# Schematic_DeLonghi_CP_original.net
KiCad netlist of a schematic drawn in EasyEDA
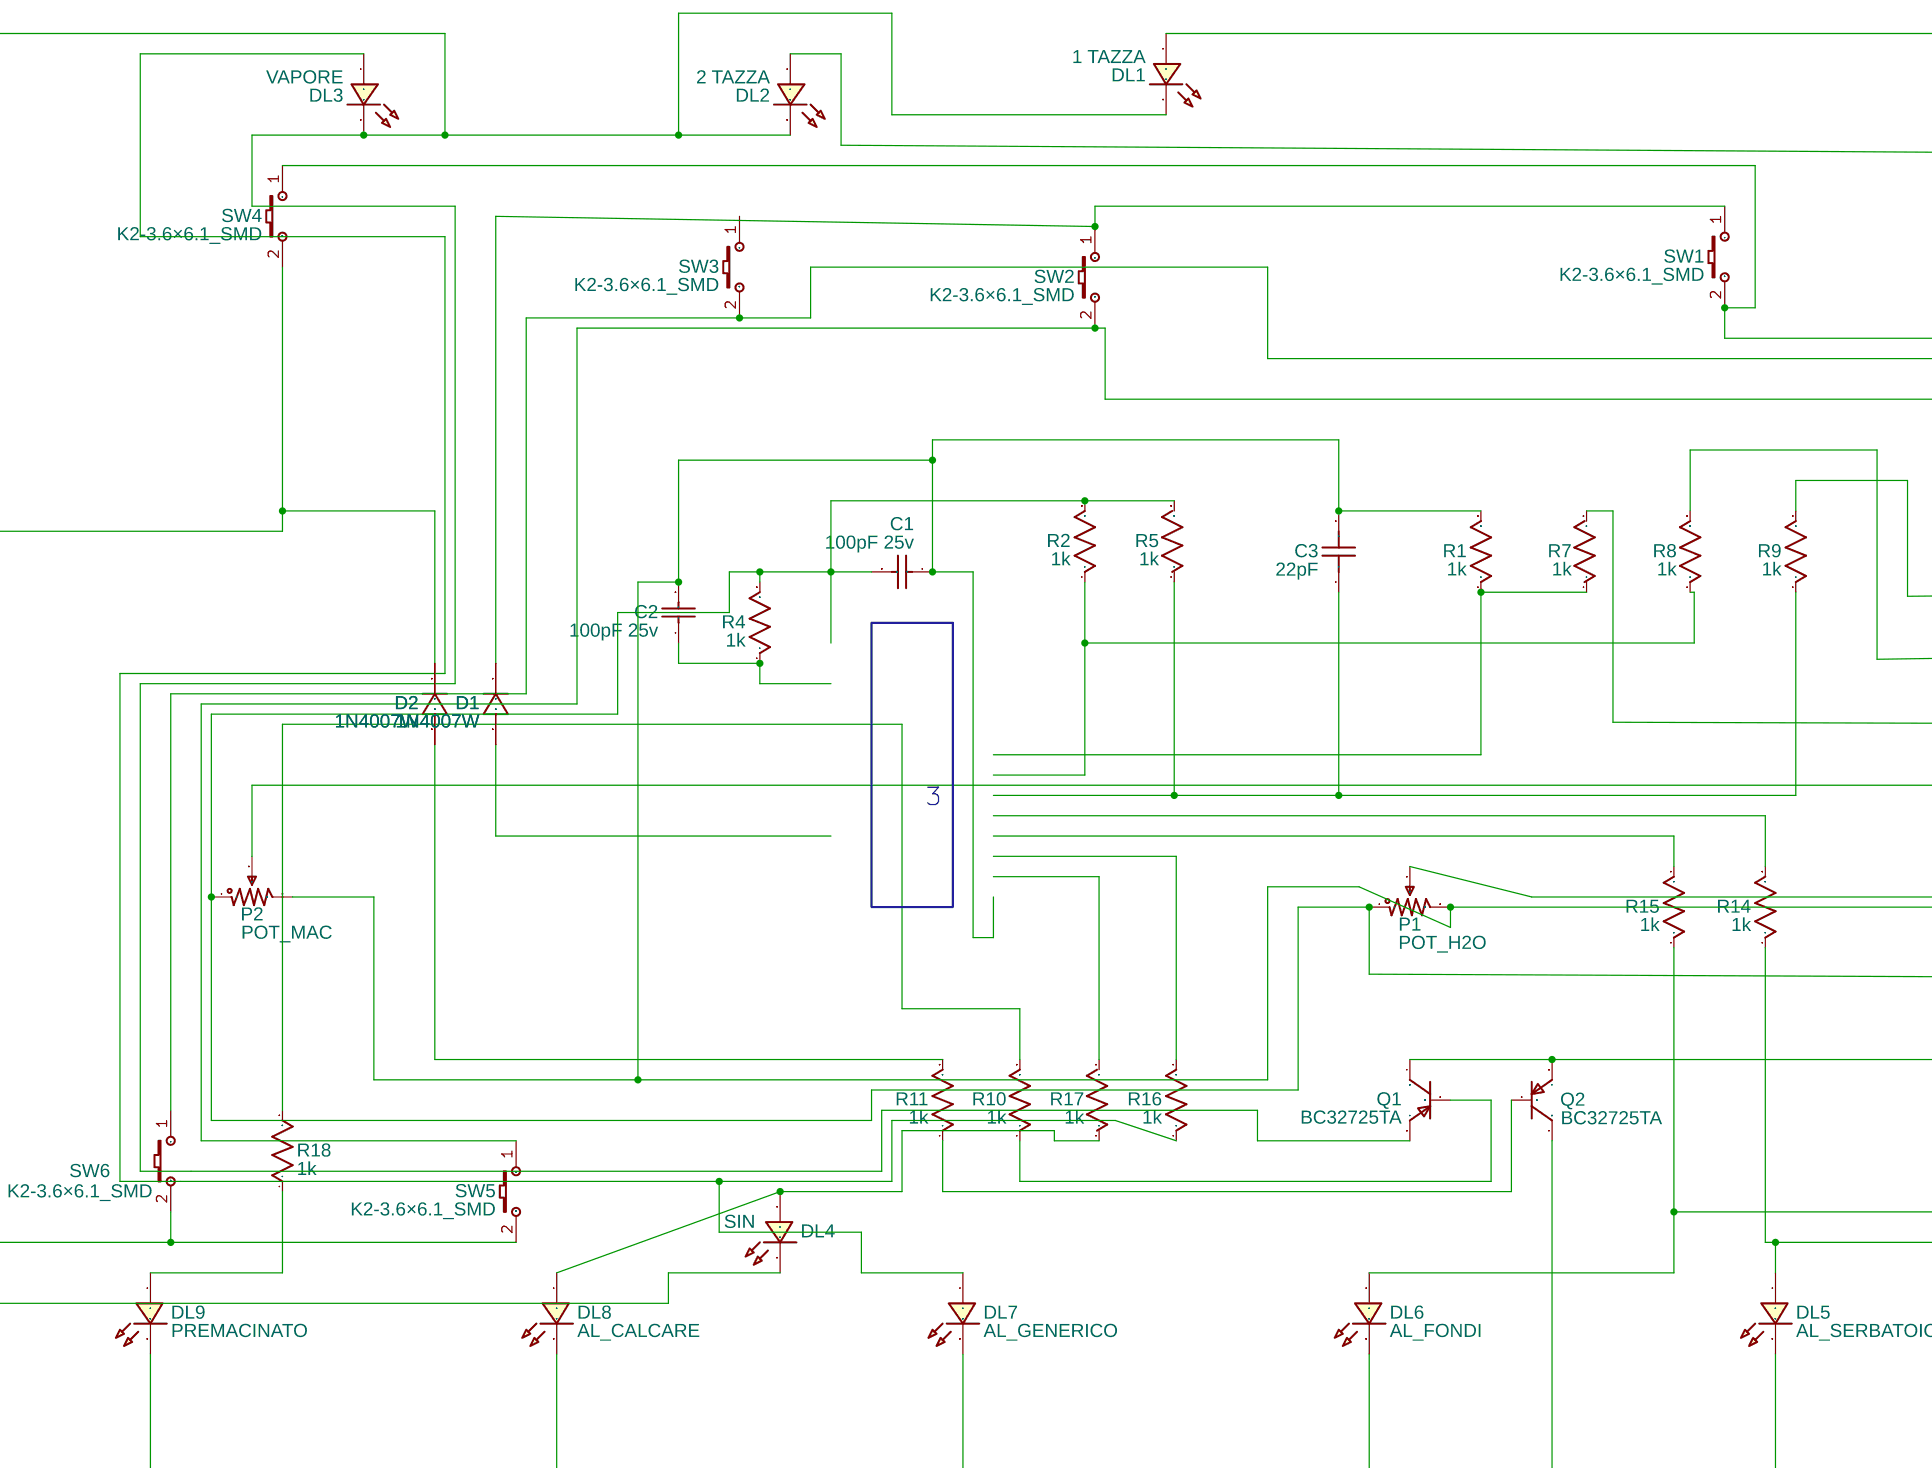
[diagram p0: schematic sheet]

(export (version "E")
  (design (tool "Eeschema 10.0.6"))
  (components
    (comp (ref "C1") (value "100pF 25v") (libsource (lib "") (part "100pF (101) 25V")))
    (comp (ref "C2") (value "100pF 25v") (libsource (lib "") (part "100pF (101) 25V_1")))
    (comp (ref "C3")
      (value "22pF")
      (fields
        (field (name "BOM_Manufacturer Part") "08051A220JAT2A")
        (field (name "BOM_Supplier Part") "C382073")
      )
      (libsource (lib "") (part "08051A220JAT2A"))
    )
    (comp (ref "D1")
      (value "1N4007W")
      (fields (field (name "BOM_Supplier Part") "C328592"))
      (libsource (lib "") (part "1N4007W"))
    )
    (comp (ref "D2")
      (value "1N4007W")
      (fields (field (name "BOM_Supplier Part") "C328592"))
      (libsource (lib "") (part "1N4007W"))
    )
    (comp (ref "DL1")
      (value "1 TAZZA")
      (fields
        (field (name "BOM_Manufacturer Part") "19-217/R6C-AL1M2VY/3T")
        (field (name "BOM_Supplier Part") "C72044")
      )
      (libsource (lib "") (part "LED-0603_R_1"))
    )
    (comp (ref "DL2")
      (value "2 TAZZA")
      (fields
        (field (name "BOM_Manufacturer Part") "19-217/R6C-AL1M2VY/3T")
        (field (name "BOM_Supplier Part") "C72044")
      )
      (libsource (lib "") (part "LED-0603_R_1"))
    )
    (comp (ref "DL3")
      (value "VAPORE")
      (fields
        (field (name "BOM_Manufacturer Part") "19-217/R6C-AL1M2VY/3T")
        (field (name "BOM_Supplier Part") "C72044")
      )
      (libsource (lib "") (part "LED-0603_R_1"))
    )
    (comp (ref "DL4")
      (value "SIN")
      (fields
        (field (name "BOM_Manufacturer Part") "19-217/R6C-AL1M2VY/3T")
        (field (name "BOM_Supplier Part") "C72044")
      )
      (libsource (lib "") (part "LED-0603_R"))
    )
    (comp (ref "DL5")
      (value "AL_SERBATOIO")
      (fields
        (field (name "BOM_Manufacturer Part") "19-217/R6C-AL1M2VY/3T")
        (field (name "BOM_Supplier Part") "C72044")
      )
      (libsource (lib "") (part "LED-0603_R"))
    )
    (comp (ref "DL6")
      (value "AL_FONDI")
      (fields
        (field (name "BOM_Manufacturer Part") "19-217/R6C-AL1M2VY/3T")
        (field (name "BOM_Supplier Part") "C72044")
      )
      (libsource (lib "") (part "LED-0603_R"))
    )
    (comp (ref "DL7")
      (value "AL_GENERICO")
      (fields
        (field (name "BOM_Manufacturer Part") "19-217/R6C-AL1M2VY/3T")
        (field (name "BOM_Supplier Part") "C72044")
      )
      (libsource (lib "") (part "LED-0603_R"))
    )
    (comp (ref "DL8")
      (value "AL_CALCARE")
      (fields
        (field (name "BOM_Manufacturer Part") "19-217/R6C-AL1M2VY/3T")
        (field (name "BOM_Supplier Part") "C72044")
      )
      (libsource (lib "") (part "LED-0603_R"))
    )
    (comp (ref "DL9")
      (value "PREMACINATO")
      (fields
        (field (name "BOM_Manufacturer Part") "19-217/R6C-AL1M2VY/3T")
        (field (name "BOM_Supplier Part") "C72044")
      )
      (libsource (lib "") (part "LED-0603_R"))
    )
    (comp (ref "P1") (value "POT_H2O") (libsource (lib "") (part "R_3386P_US")))
    (comp (ref "P2") (value "POT_MAC") (libsource (lib "") (part "R_3386P_US")))
    (comp (ref "Q1")
      (value "BC32725TA")
      (fields (field (name "BOM_Supplier Part") "C236948"))
      (libsource (lib "") (part "BC32725TA_1"))
    )
    (comp (ref "Q2")
      (value "BC32725TA")
      (fields (field (name "BOM_Supplier Part") "C236948"))
      (libsource (lib "") (part "BC32725TA"))
    )
    (comp (ref "R1") (value "1k") (libsource (lib "") (part "R_0201_US")))
    (comp (ref "R2") (value "1k") (libsource (lib "") (part "R_0201_US")))
    (comp (ref "R4") (value "1k") (libsource (lib "") (part "R_0201_US")))
    (comp (ref "R5") (value "1k") (libsource (lib "") (part "R_0201_US_2")))
    (comp (ref "R7") (value "1k") (libsource (lib "") (part "R_0201_US_2")))
    (comp (ref "R8") (value "1k") (libsource (lib "") (part "R_0201_US")))
    (comp (ref "R9") (value "1k") (libsource (lib "") (part "R_0201_US")))
    (comp (ref "R10") (value "1k") (libsource (lib "") (part "R_0201_US")))
    (comp (ref "R11") (value "1k") (libsource (lib "") (part "R_0201_US")))
    (comp (ref "R14") (value "1k") (libsource (lib "") (part "R_0201_US")))
    (comp (ref "R15") (value "1k") (libsource (lib "") (part "R_0201_US")))
    (comp (ref "R16") (value "1k") (libsource (lib "") (part "R_0201_US")))
    (comp (ref "R17") (value "1k") (libsource (lib "") (part "R_0201_US_2")))
    (comp (ref "R18") (value "1k") (libsource (lib "") (part "R_0201_US_1")))
    (comp (ref "SW1")
      (value "K2-3.6×6.1_SMD")
      (fields
        (field (name "BOM_Manufacturer Part") "K2-1107ST-A4SW-06")
        (field (name "BOM_Supplier Part") "C118141")
      )
      (libsource (lib "") (part "K2-3.6×6.1_SMD"))
    )
    (comp (ref "SW2")
      (value "K2-3.6×6.1_SMD")
      (fields
        (field (name "BOM_Manufacturer Part") "K2-1107ST-A4SW-06")
        (field (name "BOM_Supplier Part") "C118141")
      )
      (libsource (lib "") (part "K2-3.6×6.1_SMD"))
    )
    (comp (ref "SW3")
      (value "K2-3.6×6.1_SMD")
      (fields
        (field (name "BOM_Manufacturer Part") "K2-1107ST-A4SW-06")
        (field (name "BOM_Supplier Part") "C118141")
      )
      (libsource (lib "") (part "K2-3.6×6.1_SMD"))
    )
    (comp (ref "SW4")
      (value "K2-3.6×6.1_SMD")
      (fields
        (field (name "BOM_Manufacturer Part") "K2-1107ST-A4SW-06")
        (field (name "BOM_Supplier Part") "C118141")
      )
      (libsource (lib "") (part "K2-3.6×6.1_SMD"))
    )
    (comp (ref "SW5")
      (value "K2-3.6×6.1_SMD")
      (fields
        (field (name "BOM_Manufacturer Part") "K2-1107ST-A4SW-06")
        (field (name "BOM_Supplier Part") "C118141")
      )
      (libsource (lib "") (part "K2-3.6×6.1_SMD"))
    )
    (comp (ref "SW6")
      (value "K2-3.6×6.1_SMD")
      (fields
        (field (name "BOM_Manufacturer Part") "K2-1107ST-A4SW-06")
        (field (name "BOM_Supplier Part") "C118141")
      )
      (libsource (lib "") (part "K2-3.6×6.1_SMD"))
    )
  )
  (nets
    (net (code "1") (name "Net-(C1-Pad1)") (class "Default")
      (node (ref "C1") (pin "1") (pinfunction "1_1") (pintype "input"))
      (node (ref "C2") (pin "2") (pinfunction "2_2") (pintype "input"))
      (node (ref "C3") (pin "2") (pinfunction "2_2") (pintype "unspecified"))
      (node (ref "P1") (pin "3") (pinfunction "3_3") (pintype "unspecified"))
      (node (ref "P2") (pin "3") (pinfunction "3_3") (pintype "unspecified"))
      (node (ref "R1") (pin "2") (pinfunction "2_2") (pintype "unspecified"))
    )
    (net (code "2") (name "Net-(C1-Pad2)") (class "Default")
      (node (ref "C1") (pin "2") (pinfunction "2_2") (pintype "input"))
      (node (ref "P1") (pin "1") (pinfunction "1_1") (pintype "unspecified"))
      (node (ref "P2") (pin "1") (pinfunction "1_1") (pintype "unspecified"))
      (node (ref "R2") (pin "2") (pinfunction "2_2") (pintype "unspecified"))
      (node (ref "R4") (pin "2") (pinfunction "2_2") (pintype "unspecified"))
      (node (ref "R5") (pin "2") (pinfunction "2_2") (pintype "unspecified"))
    )
    (net (code "3") (name "Net-(C2-Pad1)") (class "Default")
      (node (ref "C2") (pin "1") (pinfunction "1_1") (pintype "input"))
      (node (ref "R4") (pin "1") (pinfunction "1_1") (pintype "unspecified"))
    )
    (net (code "4") (name "Net-(C3-Pad1)") (class "Default")
      (node (ref "C3") (pin "1") (pinfunction "1_1") (pintype "unspecified"))
      (node (ref "R5") (pin "1") (pinfunction "1_1") (pintype "unspecified"))
      (node (ref "R9") (pin "1") (pinfunction "1_1") (pintype "unspecified"))
    )
    (net (code "5") (name "Net-(D1-Pad1)") (class "Default")
      (node (ref "D1") (pin "1") (pinfunction "1_1") (pintype "unspecified"))
      (node (ref "SW1") (pin "1") (pinfunction "1_1") (pintype "unspecified"))
      (node (ref "SW2") (pin "1") (pinfunction "1_1") (pintype "unspecified"))
    )
    (net (code "6") (name "Net-(D2-Pad1)") (class "Default")
      (node (ref "D2") (pin "1") (pinfunction "1_1") (pintype "unspecified"))
      (node (ref "SW4") (pin "2") (pinfunction "2_2") (pintype "unspecified"))
      (node (ref "SW5") (pin "2") (pinfunction "2_2") (pintype "unspecified"))
      (node (ref "SW6") (pin "2") (pinfunction "2_2") (pintype "unspecified"))
    )
    (net (code "7") (name "Net-(D2-Pad2)") (class "Default")
      (node (ref "D2") (pin "2") (pinfunction "2_2") (pintype "unspecified"))
      (node (ref "R11") (pin "2") (pinfunction "2_2") (pintype "unspecified"))
    )
    (net (code "8") (name "Net-(DL1-Pad1)") (class "Default")
      (node (ref "DL1") (pin "1") (pinfunction "1_1") (pintype "unspecified"))
      (node (ref "DL5") (pin "1") (pinfunction "1_1") (pintype "unspecified"))
      (node (ref "R14") (pin "1") (pinfunction "1_1") (pintype "unspecified"))
    )
    (net (code "9") (name "Net-(DL2-Pad1)") (class "Default")
      (node (ref "DL2") (pin "1") (pinfunction "1_1") (pintype "unspecified"))
      (node (ref "DL6") (pin "1") (pinfunction "1_1") (pintype "unspecified"))
      (node (ref "R15") (pin "1") (pinfunction "1_1") (pintype "unspecified"))
    )
    (net (code "10") (name "Net-(DL3-Pad1)") (class "Default")
      (node (ref "DL3") (pin "1") (pinfunction "1_1") (pintype "unspecified"))
      (node (ref "DL7") (pin "1") (pinfunction "1_1") (pintype "unspecified"))
      (node (ref "R16") (pin "1") (pinfunction "1_1") (pintype "unspecified"))
    )
    (net (code "11") (name "Net-(DL4-Pad1)") (class "Default")
      (node (ref "DL4") (pin "1") (pinfunction "1_1") (pintype "unspecified"))
      (node (ref "DL8") (pin "1") (pinfunction "1_1") (pintype "unspecified"))
      (node (ref "R17") (pin "1") (pinfunction "1_1") (pintype "unspecified"))
    )
    (net (code "12") (name "Net-(DL9-Pad1)") (class "Default")
      (node (ref "DL9") (pin "1") (pinfunction "1_1") (pintype "unspecified"))
      (node (ref "R18") (pin "1") (pinfunction "1_1") (pintype "unspecified"))
    )
    (net (code "13") (name "Net-(Q1-B)") (class "Default")
      (node (ref "Q1") (pin "2") (pinfunction "B_2") (pintype "unspecified"))
      (node (ref "R10") (pin "1") (pinfunction "1_1") (pintype "unspecified"))
    )
    (net (code "14") (name "Net-(Q1-C)") (class "Default")
      (node (ref "Q1") (pin "1") (pinfunction "C_1") (pintype "unspecified"))
      (node (ref "Q2") (pin "3") (pinfunction "E_3") (pintype "unspecified"))
    )
    (net (code "15") (name "Net-(Q1-E)") (class "Default")
      (node (ref "DL1") (pin "2") (pinfunction "2_2") (pintype "unspecified"))
      (node (ref "DL2") (pin "2") (pinfunction "2_2") (pintype "unspecified"))
      (node (ref "DL3") (pin "2") (pinfunction "2_2") (pintype "unspecified"))
      (node (ref "DL4") (pin "2") (pinfunction "2_2") (pintype "unspecified"))
      (node (ref "Q1") (pin "3") (pinfunction "E_3") (pintype "unspecified"))
    )
    (net (code "16") (name "Net-(Q2-B)") (class "Default")
      (node (ref "Q2") (pin "2") (pinfunction "B_2") (pintype "unspecified"))
      (node (ref "R11") (pin "1") (pinfunction "1_1") (pintype "unspecified"))
    )
    (net (code "17") (name "Net-(Q2-C)") (class "Default")
      (node (ref "DL5") (pin "2") (pinfunction "2_2") (pintype "unspecified"))
      (node (ref "DL6") (pin "2") (pinfunction "2_2") (pintype "unspecified"))
      (node (ref "DL7") (pin "2") (pinfunction "2_2") (pintype "unspecified"))
      (node (ref "DL8") (pin "2") (pinfunction "2_2") (pintype "unspecified"))
      (node (ref "DL9") (pin "2") (pinfunction "2_2") (pintype "unspecified"))
      (node (ref "Q2") (pin "1") (pinfunction "C_1") (pintype "unspecified"))
    )
    (net (code "18") (name "Net-(R1-Pad1)") (class "Default")
      (node (ref "R1") (pin "1") (pinfunction "1_1") (pintype "unspecified"))
      (node (ref "R7") (pin "1") (pinfunction "1_1") (pintype "unspecified"))
    )
    (net (code "19") (name "Net-(R2-Pad1)") (class "Default")
      (node (ref "R2") (pin "1") (pinfunction "1_1") (pintype "unspecified"))
      (node (ref "R8") (pin "1") (pinfunction "1_1") (pintype "unspecified"))
    )
    (net (code "20") (name "Net-(R10-Pad2)") (class "Default")
      (node (ref "R10") (pin "2") (pinfunction "2_2") (pintype "unspecified"))
      (node (ref "R18") (pin "2") (pinfunction "2_2") (pintype "unspecified"))
    )
    (net (code "21") (name "Net-(SW1-Pad2)") (class "Default")
      (node (ref "SW1") (pin "2") (pinfunction "2_2") (pintype "unspecified"))
      (node (ref "SW4") (pin "1") (pinfunction "1_1") (pintype "unspecified"))
    )
    (net (code "22") (name "Net-(SW2-Pad2)") (class "Default")
      (node (ref "SW2") (pin "2") (pinfunction "2_2") (pintype "unspecified"))
      (node (ref "SW5") (pin "1") (pinfunction "1_1") (pintype "unspecified"))
    )
    (net (code "23") (name "Net-(SW3-Pad2)") (class "Default")
      (node (ref "SW3") (pin "2") (pinfunction "2_2") (pintype "unspecified"))
      (node (ref "SW6") (pin "1") (pinfunction "1_1") (pintype "unspecified"))
    )
    (net (code "24") (name "unconnected-(D1-Pad2)") (class "Default")
      (node (ref "D1") (pin "2") (pinfunction "2_2") (pintype "unspecified"))
    )
    (net (code "25") (name "unconnected-(P1-Pad2)") (class "Default")
      (node (ref "P1") (pin "2") (pinfunction "2_2") (pintype "unspecified"))
    )
    (net (code "26") (name "unconnected-(P2-Pad2)") (class "Default")
      (node (ref "P2") (pin "2") (pinfunction "2_2") (pintype "unspecified"))
    )
    (net (code "27") (name "unconnected-(R7-Pad2)") (class "Default")
      (node (ref "R7") (pin "2") (pinfunction "2_2") (pintype "unspecified"))
    )
    (net (code "28") (name "unconnected-(R8-Pad2)") (class "Default")
      (node (ref "R8") (pin "2") (pinfunction "2_2") (pintype "unspecified"))
    )
    (net (code "29") (name "unconnected-(R9-Pad2)") (class "Default")
      (node (ref "R9") (pin "2") (pinfunction "2_2") (pintype "unspecified"))
    )
    (net (code "30") (name "unconnected-(R14-Pad2)") (class "Default")
      (node (ref "R14") (pin "2") (pinfunction "2_2") (pintype "unspecified"))
    )
    (net (code "31") (name "unconnected-(R15-Pad2)") (class "Default")
      (node (ref "R15") (pin "2") (pinfunction "2_2") (pintype "unspecified"))
    )
    (net (code "32") (name "unconnected-(R16-Pad2)") (class "Default")
      (node (ref "R16") (pin "2") (pinfunction "2_2") (pintype "unspecified"))
    )
    (net (code "33") (name "unconnected-(R17-Pad2)") (class "Default")
      (node (ref "R17") (pin "2") (pinfunction "2_2") (pintype "unspecified"))
    )
    (net (code "34") (name "unconnected-(SW3-Pad1)") (class "Default")
      (node (ref "SW3") (pin "1") (pinfunction "1_1") (pintype "unspecified"))
    )
  )
)
